# Sheet2.net
KiCad netlist of a schematic drawn in Altium Designer
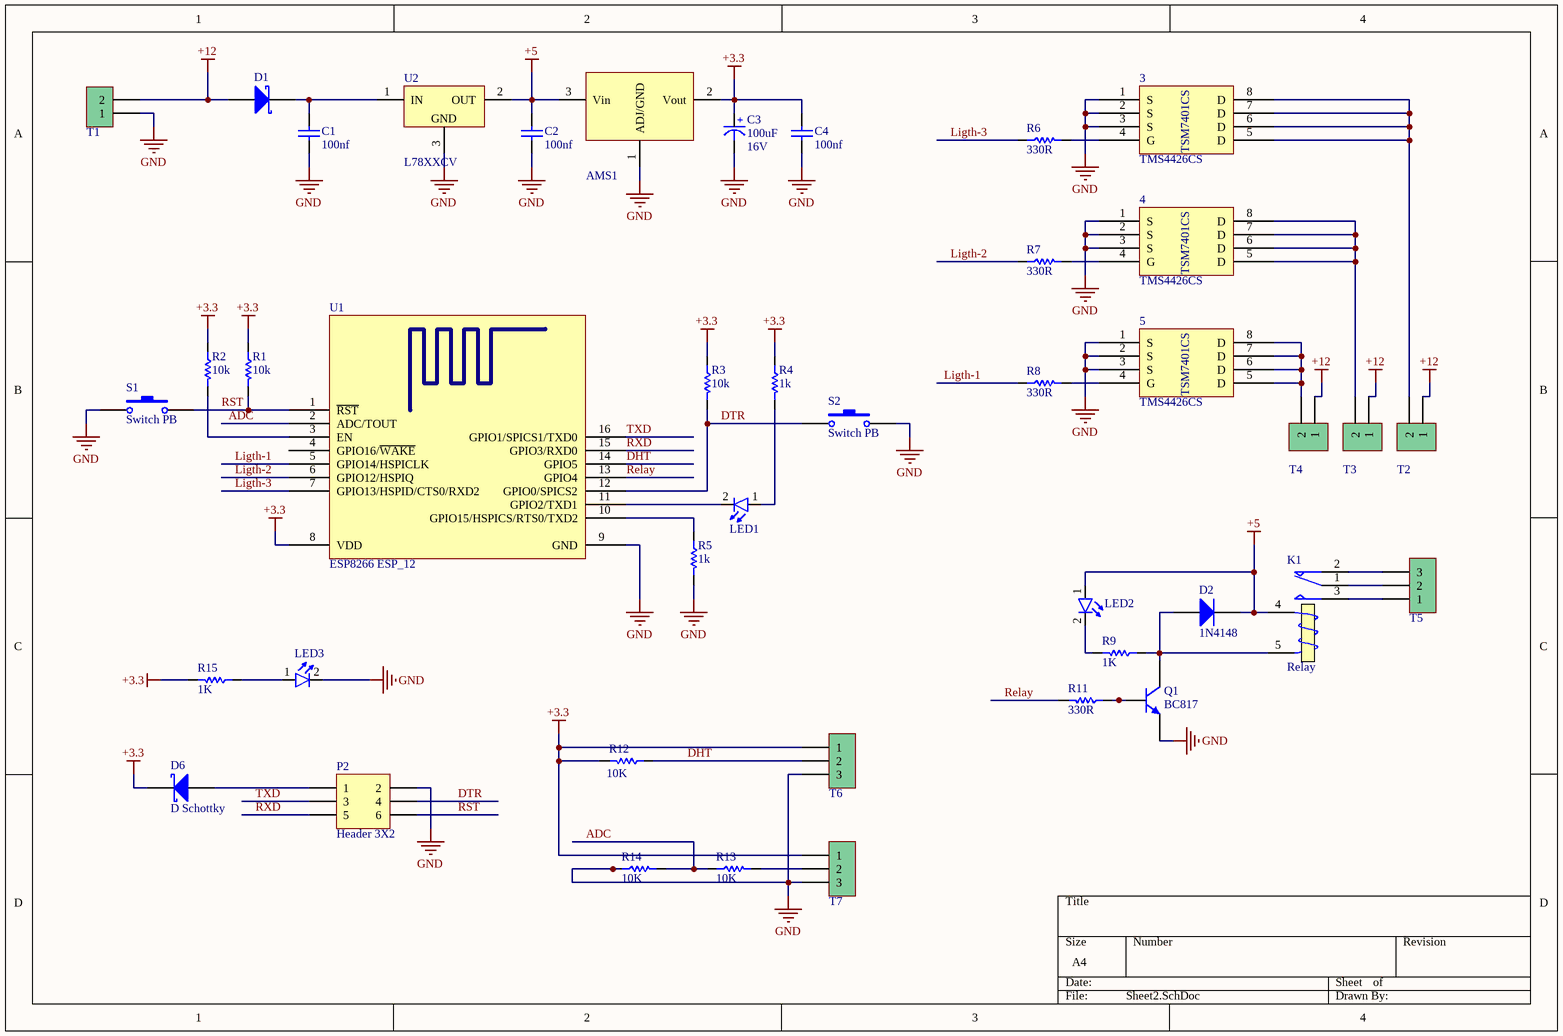
[diagram p0: Sheet2.SchDoc]

(export (version "E")
  (design (tool "Eeschema 10.0.6"))
  (components
    (comp (ref "3") (value "TMS4426CS") (footprint "sop8") (libsource (lib "Schlib1") (part "TMS4426CS")))
    (comp (ref "4") (value "TMS4426CS") (footprint "sop8") (libsource (lib "Schlib1") (part "TMS4426CS")))
    (comp (ref "5") (value "TMS4426CS") (footprint "sop8") (libsource (lib "Schlib1") (part "TMS4426CS")))
    (comp (ref "AMS1")
      (value "AMS1117")
      (footprint "AMS1117")
      (description "LDO 3.3V/5V/12V")
      (libsource (lib "ICs") (part "AMS1117"))
    )
    (comp (ref "C1")
      (value "100nf")
      (footprint "C1206")
      (description "Capacitor (Semiconductor SIM Model)")
      (fields (field (name "Comment") "Cap Semi") (field (name "PUBLISHER") "Altium Limited"))
      (libsource (lib "Miscellaneous Devices") (part "Cap Semi"))
    )
    (comp (ref "C2")
      (value "100nf")
      (footprint "C1206")
      (description "Capacitor (Semiconductor SIM Model)")
      (fields (field (name "Comment") "Cap Semi") (field (name "PUBLISHER") "Altium Limited"))
      (libsource (lib "Miscellaneous Devices") (part "Cap Semi"))
    )
    (comp (ref "C3")
      (value "100uF")
      (footprint "cap 02")
      (description "Polar Capacitor")
      (fields (field (name "VOLTAGE") "16V") (field (name "DESIGNER") "Saeid Jorablo"))
      (libsource (lib "Electrovolt Lib") (part "Cap-Polar"))
    )
    (comp (ref "C4")
      (value "100nf")
      (footprint "C1206")
      (description "Capacitor (Semiconductor SIM Model)")
      (fields (field (name "Comment") "Cap Semi") (field (name "PUBLISHER") "Altium Limited"))
      (libsource (lib "Miscellaneous Devices") (part "Cap Semi"))
    )
    (comp (ref "D1")
      (value "~")
      (footprint "SMB")
      (fields (field (name "PUBLISHER") "Altium Limited"))
      (libsource (lib "Miscellaneous Devices") (part "D Schottky"))
    )
    (comp (ref "D2")
      (value "1N4148")
      (footprint "SMB")
      (description "High Conductance Fast Diode")
      (fields (field (name "PUBLISHER") "Altium Limited"))
      (libsource (lib "Electrovolt Lib") (part "Diode 1N4148"))
    )
    (comp (ref "D6")
      (value "D Schottky")
      (footprint "SMB")
      (description "Schottky Diode")
      (fields (field (name "PUBLISHER") "Altium Limited"))
      (libsource (lib "Miscellaneous Devices") (part "D Schottky"))
    )
    (comp (ref "K1")
      (value "Relay")
      (footprint "Relay 18.85x15.35x15.70")
      (description "SPDT Relay")
      (fields (field (name "DESIGNER") "Eng. Saeid Jorablo"))
      (libsource (lib "Electrovolt Lib") (part "Relay"))
    )
    (comp (ref "LED1")
      (value "Red")
      (footprint "LED-3mm")
      (description "LED")
      (fields (field (name "DESIGNER") "Saeid Jorablo"))
      (libsource (lib "Electrovolt Lib") (part "LED"))
    )
    (comp (ref "LED2")
      (value "Red")
      (footprint "LED-3mm")
      (description "LED")
      (fields (field (name "DESIGNER") "Saeid Jorablo"))
      (libsource (lib "Electrovolt Lib") (part "LED"))
    )
    (comp (ref "LED3")
      (value "Red")
      (footprint "LED-3mm")
      (description "LED")
      (fields (field (name "DESIGNER") "Saeid Jorablo"))
      (libsource (lib "Electrovolt Lib") (part "LED"))
    )
    (comp (ref "P2")
      (value "Header 3X2")
      (footprint "HDR2X3")
      (description "Header, 3-Pin, Dual row")
      (fields (field (name "PUBLISHER") "Altium Limited"))
      (libsource (lib "Miscellaneous Connectors") (part "Header 3X2"))
    )
    (comp (ref "Q1")
      (value "BC817")
      (footprint "SOT23_BEC_N")
      (description "NPN Bipolar Transistor")
      (fields (field (name "PUBLISHER") "Altium Limited"))
      (libsource (lib "Electrovolt Lib") (part "NPN"))
    )
    (comp (ref "R1")
      (value "10k")
      (footprint "RES 1206 (3216X08L)")
      (description "Resistor")
      (fields (field (name "TOLERANCE") "5%") (field (name "POWER") "1/8 W"))
      (libsource (lib "Electrovolt Lib") (part "Resistor"))
    )
    (comp (ref "R2")
      (value "10k")
      (footprint "RES 1206 (3216X08L)")
      (description "Resistor")
      (fields (field (name "TOLERANCE") "5%") (field (name "POWER") "1/8 W"))
      (libsource (lib "Electrovolt Lib") (part "Resistor"))
    )
    (comp (ref "R3")
      (value "10k")
      (footprint "RES 1206 (3216X08L)")
      (description "Resistor")
      (fields (field (name "TOLERANCE") "5%") (field (name "POWER") "1/8 W"))
      (libsource (lib "Electrovolt Lib") (part "Resistor"))
    )
    (comp (ref "R4")
      (value "1k")
      (footprint "RES 1206 (3216X08L)")
      (description "Resistor")
      (fields (field (name "TOLERANCE") "5%") (field (name "POWER") "1/8 W"))
      (libsource (lib "Electrovolt Lib") (part "Resistor"))
    )
    (comp (ref "R5")
      (value "1k")
      (footprint "RES 1206 (3216X08L)")
      (description "Resistor")
      (fields (field (name "TOLERANCE") "5%") (field (name "POWER") "1/8 W"))
      (libsource (lib "Electrovolt Lib") (part "Resistor"))
    )
    (comp (ref "R6")
      (value "330R")
      (footprint "RES 1206 (3216X08L)")
      (description "Resistor")
      (fields (field (name "TOLERANCE") "5%") (field (name "POWER") "1/8 W"))
      (libsource (lib "Electrovolt Lib") (part "Resistor"))
    )
    (comp (ref "R7")
      (value "330R")
      (footprint "RES 1206 (3216X08L)")
      (description "Resistor")
      (fields (field (name "TOLERANCE") "5%") (field (name "POWER") "1/8 W"))
      (libsource (lib "Electrovolt Lib") (part "Resistor"))
    )
    (comp (ref "R8")
      (value "330R")
      (footprint "RES 1206 (3216X08L)")
      (description "Resistor")
      (fields (field (name "TOLERANCE") "5%") (field (name "POWER") "1/8 W"))
      (libsource (lib "Electrovolt Lib") (part "Resistor"))
    )
    (comp (ref "R9")
      (value "1K")
      (footprint "RES 1206 (3216X08L)")
      (description "Resistor")
      (fields (field (name "TOLERANCE") "5%") (field (name "POWER") "1/8 W"))
      (libsource (lib "Electrovolt Lib") (part "Resistor"))
    )
    (comp (ref "R11")
      (value "330R")
      (footprint "RES 1206 (3216X08L)")
      (description "Resistor")
      (fields (field (name "TOLERANCE") "5%") (field (name "POWER") "1/8 W"))
      (libsource (lib "Electrovolt Lib") (part "Resistor"))
    )
    (comp (ref "R12")
      (value "10K")
      (footprint "RES 1206 (3216X08L)")
      (description "Resistor")
      (fields (field (name "TOLERANCE") "5%") (field (name "POWER") "1/8 W"))
      (libsource (lib "Electrovolt Lib") (part "Resistor"))
    )
    (comp (ref "R13")
      (value "10K")
      (footprint "RES 1206 (3216X08L)")
      (description "Resistor")
      (fields (field (name "TOLERANCE") "5%") (field (name "POWER") "1/8 W"))
      (libsource (lib "Electrovolt Lib") (part "Resistor"))
    )
    (comp (ref "R14")
      (value "10K")
      (footprint "RES 1206 (3216X08L)")
      (description "Resistor")
      (fields (field (name "TOLERANCE") "5%") (field (name "POWER") "1/8 W"))
      (libsource (lib "Electrovolt Lib") (part "Resistor"))
    )
    (comp (ref "R15")
      (value "1K")
      (footprint "RES 1206 (3216X08L)")
      (description "Resistor")
      (fields (field (name "TOLERANCE") "5%") (field (name "POWER") "1/8 W"))
      (libsource (lib "Electrovolt Lib") (part "Resistor"))
    )
    (comp (ref "S1")
      (value "Switch PB")
      (footprint "button_R")
      (description "Push Button Switch")
      (libsource (lib "Electrovolt Lib") (part "Switch PB"))
    )
    (comp (ref "S2")
      (value "Switch PB")
      (footprint "button_R")
      (description "Push Button Switch")
      (libsource (lib "Electrovolt Lib") (part "Switch PB"))
    )
    (comp (ref "T1")
      (value "Phoenix terminal")
      (footprint "phoenix terminal 2")
      (description "Terminal 2 Pin")
      (fields (field (name "DESIGNER") "Seyed Mohsen Ghasemain") (field (name "E-MAIL") "picpars@gmail.com"))
      (libsource (lib "") (part "Phoenix terminal 2_1"))
    )
    (comp (ref "T2")
      (value "Phoenix terminal")
      (footprint "phoenix terminal 2")
      (description "Terminal 2 Pin")
      (fields (field (name "DESIGNER") "Seyed Mohsen Ghasemain") (field (name "E-MAIL") "picpars@gmail.com"))
      (libsource (lib "usefully_Library") (part "Phoenix terminal 2"))
    )
    (comp (ref "T3")
      (value "Phoenix terminal")
      (footprint "phoenix terminal 2")
      (description "Terminal 2 Pin")
      (fields (field (name "DESIGNER") "Seyed Mohsen Ghasemain") (field (name "E-MAIL") "picpars@gmail.com"))
      (libsource (lib "usefully_Library") (part "Phoenix terminal 2"))
    )
    (comp (ref "T4")
      (value "Phoenix terminal")
      (footprint "phoenix terminal 2")
      (description "Terminal 2 Pin")
      (fields (field (name "DESIGNER") "Seyed Mohsen Ghasemain") (field (name "E-MAIL") "picpars@gmail.com"))
      (libsource (lib "usefully_Library") (part "Phoenix terminal 2"))
    )
    (comp (ref "T5")
      (value "Phoenix terminal")
      (footprint "phoenix terminal 3")
      (description "Terminal 3 Pin")
      (fields (field (name "DESIGNER") "Seyed Mohsen Ghasemain") (field (name "E-MAIL") "picpars@gmail.com"))
      (libsource (lib "usefully_Library") (part "Phoenix terminal 3"))
    )
    (comp (ref "T6")
      (value "Phoenix terminal")
      (footprint "phoenix terminal 3")
      (description "Terminal 3 Pin")
      (fields (field (name "DESIGNER") "Seyed Mohsen Ghasemain") (field (name "E-MAIL") "picpars@gmail.com"))
      (libsource (lib "") (part "Phoenix terminal 3_1"))
    )
    (comp (ref "T7")
      (value "Phoenix terminal")
      (footprint "phoenix terminal 3")
      (description "Terminal 3 Pin")
      (fields (field (name "DESIGNER") "Seyed Mohsen Ghasemain") (field (name "E-MAIL") "picpars@gmail.com"))
      (libsource (lib "") (part "Phoenix terminal 3_1"))
    )
    (comp (ref "U1")
      (value "ESP8266 ESP_12")
      (footprint "ESP8266:ESP8266 ESP_12")
      (description "ESP8266 ESP-12")
      (fields (field (name "PUBLISHER") "Cynetik Group") (field (name "LATESTREVIEWER") "Zion Blue"))
      (libsource (lib "ESP8266") (part "ESP8266 ESP_12"))
    )
    (comp (ref "U2")
      (value "L78XXCV")
      (footprint "78XXCV - Right")
      (description "Fixed Voltage Regulator")
      (fields (field (name "DESIGNER") "Saeid Jorablo"))
      (libsource (lib "Electrovolt Lib") (part "L78XXCV"))
    )
  )
  (nets
    (net (code "1") (name "+3.3") (class "Default")
      (node (ref "AMS1") (pin "2") (pinfunction "Vout_2") (pintype "passive"))
      (node (ref "C3") (pin "1") (pinfunction "+_1") (pintype "passive"))
      (node (ref "C4") (pin "2") (pinfunction "2_2") (pintype "passive"))
      (node (ref "D6") (pin "2") (pinfunction "K_2") (pintype "passive"))
      (node (ref "R1") (pin "1") (pinfunction "1_1") (pintype "passive"))
      (node (ref "R12") (pin "2") (pinfunction "2_2") (pintype "passive"))
      (node (ref "R15") (pin "2") (pinfunction "2_2") (pintype "passive"))
      (node (ref "R2") (pin "1") (pinfunction "1_1") (pintype "passive"))
      (node (ref "R3") (pin "1") (pinfunction "1_1") (pintype "passive"))
      (node (ref "R4") (pin "1") (pinfunction "1_1") (pintype "passive"))
      (node (ref "T6") (pin "1") (pinfunction "1_1") (pintype "passive"))
      (node (ref "T7") (pin "1") (pinfunction "1_1") (pintype "passive"))
      (node (ref "U1") (pin "8") (pinfunction "VDD_8") (pintype "passive"))
    )
    (net (code "2") (name "+5") (class "Default")
      (node (ref "AMS1") (pin "3") (pinfunction "Vin_3") (pintype "passive"))
      (node (ref "C2") (pin "2") (pinfunction "2_2") (pintype "passive"))
      (node (ref "D2") (pin "2") (pinfunction "K_2") (pintype "passive"))
      (node (ref "K1") (pin "4") (pinfunction "T1_4") (pintype "passive"))
      (node (ref "LED2") (pin "1") (pinfunction "A_1") (pintype "passive"))
      (node (ref "U2") (pin "2") (pinfunction "OUT_2") (pintype "passive"))
    )
    (net (code "3") (name "+12") (class "Default")
      (node (ref "D1") (pin "1") (pinfunction "A_1") (pintype "passive"))
      (node (ref "T1") (pin "2") (pinfunction "2_2") (pintype "passive"))
      (node (ref "T2") (pin "1") (pinfunction "1_1") (pintype "passive"))
      (node (ref "T3") (pin "1") (pinfunction "1_1") (pintype "passive"))
      (node (ref "T4") (pin "1") (pinfunction "1_1") (pintype "passive"))
    )
    (net (code "4") (name "/ADC") (class "Default")
      (node (ref "R13") (pin "1") (pinfunction "1_1") (pintype "passive"))
      (node (ref "R14") (pin "2") (pinfunction "2_2") (pintype "passive"))
      (node (ref "U1") (pin "2") (pinfunction "ADC/TOUT_2") (pintype "passive"))
    )
    (net (code "5") (name "/DHT") (class "Default")
      (node (ref "R12") (pin "1") (pinfunction "1_1") (pintype "passive"))
      (node (ref "T6") (pin "2") (pinfunction "2_2") (pintype "passive"))
      (node (ref "U1") (pin "14") (pinfunction "GPIO5_14") (pintype "passive"))
    )
    (net (code "6") (name "/DTR") (class "Default")
      (node (ref "P2") (pin "4") (pinfunction "4_4") (pintype "passive"))
      (node (ref "R3") (pin "2") (pinfunction "2_2") (pintype "passive"))
      (node (ref "S2") (pin "1") (pinfunction "1_1") (pintype "passive"))
      (node (ref "U1") (pin "12") (pinfunction "GPIO0/SPICS2_12") (pintype "passive"))
    )
    (net (code "7") (name "/Ligth-1") (class "Default")
      (node (ref "R8") (pin "1") (pinfunction "1_1") (pintype "passive"))
      (node (ref "U1") (pin "5") (pinfunction "GPIO14/HSPICLK_5") (pintype "passive"))
    )
    (net (code "8") (name "/Ligth-2") (class "Default")
      (node (ref "R7") (pin "1") (pinfunction "1_1") (pintype "passive"))
      (node (ref "U1") (pin "6") (pinfunction "GPIO12/HSPIQ_6") (pintype "passive"))
    )
    (net (code "9") (name "/Ligth-3") (class "Default")
      (node (ref "R6") (pin "1") (pinfunction "1_1") (pintype "passive"))
      (node (ref "U1") (pin "7") (pinfunction "GPIO13/HSPID/CTS0/RXD2_7") (pintype "passive"))
    )
    (net (code "10") (name "/RST") (class "Default")
      (node (ref "P2") (pin "6") (pinfunction "6_6") (pintype "passive"))
      (node (ref "R1") (pin "2") (pinfunction "2_2") (pintype "passive"))
      (node (ref "S1") (pin "2") (pinfunction "2_2") (pintype "passive"))
      (node (ref "U1") (pin "1") (pinfunction "~{RST}_1") (pintype "passive"))
    )
    (net (code "11") (name "/RXD") (class "Default")
      (node (ref "P2") (pin "5") (pinfunction "5_5") (pintype "passive"))
      (node (ref "U1") (pin "15") (pinfunction "GPIO3/RXD0_15") (pintype "passive"))
    )
    (net (code "12") (name "/Relay") (class "Default")
      (node (ref "R11") (pin "2") (pinfunction "2_2") (pintype "passive"))
      (node (ref "U1") (pin "13") (pinfunction "GPIO4_13") (pintype "passive"))
    )
    (net (code "13") (name "/TXD") (class "Default")
      (node (ref "P2") (pin "3") (pinfunction "3_3") (pintype "passive"))
      (node (ref "U1") (pin "16") (pinfunction "GPIO1/SPICS1/TXD0_16") (pintype "passive"))
    )
    (net (code "14") (name "GND") (class "Default")
      (node (ref "3") (pin "1") (pinfunction "S_1") (pintype "passive"))
      (node (ref "3") (pin "2") (pinfunction "S_2") (pintype "passive"))
      (node (ref "3") (pin "3") (pinfunction "S_3") (pintype "passive"))
      (node (ref "4") (pin "1") (pinfunction "S_1") (pintype "passive"))
      (node (ref "4") (pin "2") (pinfunction "S_2") (pintype "passive"))
      (node (ref "4") (pin "3") (pinfunction "S_3") (pintype "passive"))
      (node (ref "5") (pin "1") (pinfunction "S_1") (pintype "passive"))
      (node (ref "5") (pin "2") (pinfunction "S_2") (pintype "passive"))
      (node (ref "5") (pin "3") (pinfunction "S_3") (pintype "passive"))
      (node (ref "AMS1") (pin "1") (pinfunction "ADJ/GND_1") (pintype "passive"))
      (node (ref "C1") (pin "1") (pinfunction "1_1") (pintype "passive"))
      (node (ref "C2") (pin "1") (pinfunction "1_1") (pintype "passive"))
      (node (ref "C3") (pin "2") (pinfunction "-_2") (pintype "passive"))
      (node (ref "C4") (pin "1") (pinfunction "1_1") (pintype "passive"))
      (node (ref "LED3") (pin "2") (pinfunction "K_2") (pintype "passive"))
      (node (ref "P2") (pin "2") (pinfunction "2_2") (pintype "passive"))
      (node (ref "Q1") (pin "2") (pinfunction "E_2") (pintype "passive"))
      (node (ref "R14") (pin "1") (pinfunction "1_1") (pintype "passive"))
      (node (ref "R5") (pin "2") (pinfunction "2_2") (pintype "passive"))
      (node (ref "S1") (pin "1") (pinfunction "1_1") (pintype "passive"))
      (node (ref "S2") (pin "2") (pinfunction "2_2") (pintype "passive"))
      (node (ref "T1") (pin "1") (pinfunction "1_1") (pintype "passive"))
      (node (ref "T6") (pin "3") (pinfunction "3_3") (pintype "passive"))
      (node (ref "T7") (pin "3") (pinfunction "3_3") (pintype "passive"))
      (node (ref "U1") (pin "9") (pinfunction "GND_9") (pintype "passive"))
      (node (ref "U2") (pin "3") (pinfunction "GND_3") (pintype "passive"))
    )
    (net (code "15") (name "Net-(3-D-Pad5)") (class "Default")
      (node (ref "3") (pin "5") (pinfunction "D_5") (pintype "passive"))
      (node (ref "3") (pin "6") (pinfunction "D_6") (pintype "passive"))
      (node (ref "3") (pin "7") (pinfunction "D_7") (pintype "passive"))
      (node (ref "3") (pin "8") (pinfunction "D_8") (pintype "passive"))
      (node (ref "T2") (pin "2") (pinfunction "2_2") (pintype "passive"))
    )
    (net (code "16") (name "Net-(3-G)") (class "Default")
      (node (ref "3") (pin "4") (pinfunction "G_4") (pintype "passive"))
      (node (ref "R6") (pin "2") (pinfunction "2_2") (pintype "passive"))
    )
    (net (code "17") (name "Net-(4-D-Pad5)") (class "Default")
      (node (ref "4") (pin "5") (pinfunction "D_5") (pintype "passive"))
      (node (ref "4") (pin "6") (pinfunction "D_6") (pintype "passive"))
      (node (ref "4") (pin "7") (pinfunction "D_7") (pintype "passive"))
      (node (ref "4") (pin "8") (pinfunction "D_8") (pintype "passive"))
      (node (ref "T3") (pin "2") (pinfunction "2_2") (pintype "passive"))
    )
    (net (code "18") (name "Net-(4-G)") (class "Default")
      (node (ref "4") (pin "4") (pinfunction "G_4") (pintype "passive"))
      (node (ref "R7") (pin "2") (pinfunction "2_2") (pintype "passive"))
    )
    (net (code "19") (name "Net-(5-D-Pad5)") (class "Default")
      (node (ref "5") (pin "5") (pinfunction "D_5") (pintype "passive"))
      (node (ref "5") (pin "6") (pinfunction "D_6") (pintype "passive"))
      (node (ref "5") (pin "7") (pinfunction "D_7") (pintype "passive"))
      (node (ref "5") (pin "8") (pinfunction "D_8") (pintype "passive"))
      (node (ref "T4") (pin "2") (pinfunction "2_2") (pintype "passive"))
    )
    (net (code "20") (name "Net-(5-G)") (class "Default")
      (node (ref "5") (pin "4") (pinfunction "G_4") (pintype "passive"))
      (node (ref "R8") (pin "2") (pinfunction "2_2") (pintype "passive"))
    )
    (net (code "21") (name "Net-(D1-K)") (class "Default")
      (node (ref "C1") (pin "2") (pinfunction "2_2") (pintype "passive"))
      (node (ref "D1") (pin "2") (pinfunction "K_2") (pintype "passive"))
      (node (ref "U2") (pin "1") (pinfunction "IN_1") (pintype "passive"))
    )
    (net (code "22") (name "Net-(D2-A)") (class "Default")
      (node (ref "D2") (pin "1") (pinfunction "A_1") (pintype "passive"))
      (node (ref "K1") (pin "5") (pinfunction "T2_5") (pintype "passive"))
      (node (ref "Q1") (pin "3") (pinfunction "C_3") (pintype "passive"))
      (node (ref "R9") (pin "1") (pinfunction "1_1") (pintype "passive"))
    )
    (net (code "23") (name "Net-(D6-A)") (class "Default")
      (node (ref "D6") (pin "1") (pinfunction "A_1") (pintype "passive"))
      (node (ref "P2") (pin "1") (pinfunction "1_1") (pintype "passive"))
    )
    (net (code "24") (name "Net-(K1-COM)") (class "Default")
      (node (ref "K1") (pin "1") (pinfunction "COM_1") (pintype "passive"))
      (node (ref "T5") (pin "2") (pinfunction "2_2") (pintype "passive"))
    )
    (net (code "25") (name "Net-(K1-NC)") (class "Default")
      (node (ref "K1") (pin "2") (pinfunction "NC_2") (pintype "passive"))
      (node (ref "T5") (pin "3") (pinfunction "3_3") (pintype "passive"))
    )
    (net (code "26") (name "Net-(K1-NO)") (class "Default")
      (node (ref "K1") (pin "3") (pinfunction "NO_3") (pintype "passive"))
      (node (ref "T5") (pin "1") (pinfunction "1_1") (pintype "passive"))
    )
    (net (code "27") (name "Net-(LED1-A)") (class "Default")
      (node (ref "LED1") (pin "1") (pinfunction "A_1") (pintype "passive"))
      (node (ref "R4") (pin "2") (pinfunction "2_2") (pintype "passive"))
    )
    (net (code "28") (name "Net-(LED1-K)") (class "Default")
      (node (ref "LED1") (pin "2") (pinfunction "K_2") (pintype "passive"))
      (node (ref "U1") (pin "11") (pinfunction "GPIO2/TXD1_11") (pintype "passive"))
    )
    (net (code "29") (name "Net-(LED2-K)") (class "Default")
      (node (ref "LED2") (pin "2") (pinfunction "K_2") (pintype "passive"))
      (node (ref "R9") (pin "2") (pinfunction "2_2") (pintype "passive"))
    )
    (net (code "30") (name "Net-(LED3-A)") (class "Default")
      (node (ref "LED3") (pin "1") (pinfunction "A_1") (pintype "passive"))
      (node (ref "R15") (pin "1") (pinfunction "1_1") (pintype "passive"))
    )
    (net (code "31") (name "Net-(Q1-B)") (class "Default")
      (node (ref "Q1") (pin "1") (pinfunction "B_1") (pintype "passive"))
      (node (ref "R11") (pin "1") (pinfunction "1_1") (pintype "passive"))
    )
    (net (code "32") (name "Net-(R13-Pad2)") (class "Default")
      (node (ref "R13") (pin "2") (pinfunction "2_2") (pintype "passive"))
      (node (ref "T7") (pin "2") (pinfunction "2_2") (pintype "passive"))
    )
    (net (code "33") (name "Net-(U1-EN)") (class "Default")
      (node (ref "R2") (pin "2") (pinfunction "2_2") (pintype "passive"))
      (node (ref "U1") (pin "3") (pinfunction "EN_3") (pintype "passive"))
    )
    (net (code "34") (name "Net-(U1-GPIO15{slash}HSPICS{slash}RTS0{slash}TXD2)") (class "Default")
      (node (ref "R5") (pin "1") (pinfunction "1_1") (pintype "passive"))
      (node (ref "U1") (pin "10") (pinfunction "GPIO15/HSPICS/RTS0/TXD2_10") (pintype "passive"))
    )
    (net (code "35") (name "unconnected-(U1-GPIO16{slash}~{WAKE}-Pad4)") (class "Default")
      (node (ref "U1") (pin "4") (pinfunction "GPIO16/~{WAKE}_4") (pintype "passive"))
    )
  )
)
